# SD.net
KiCad netlist of a schematic drawn in Altium Designer
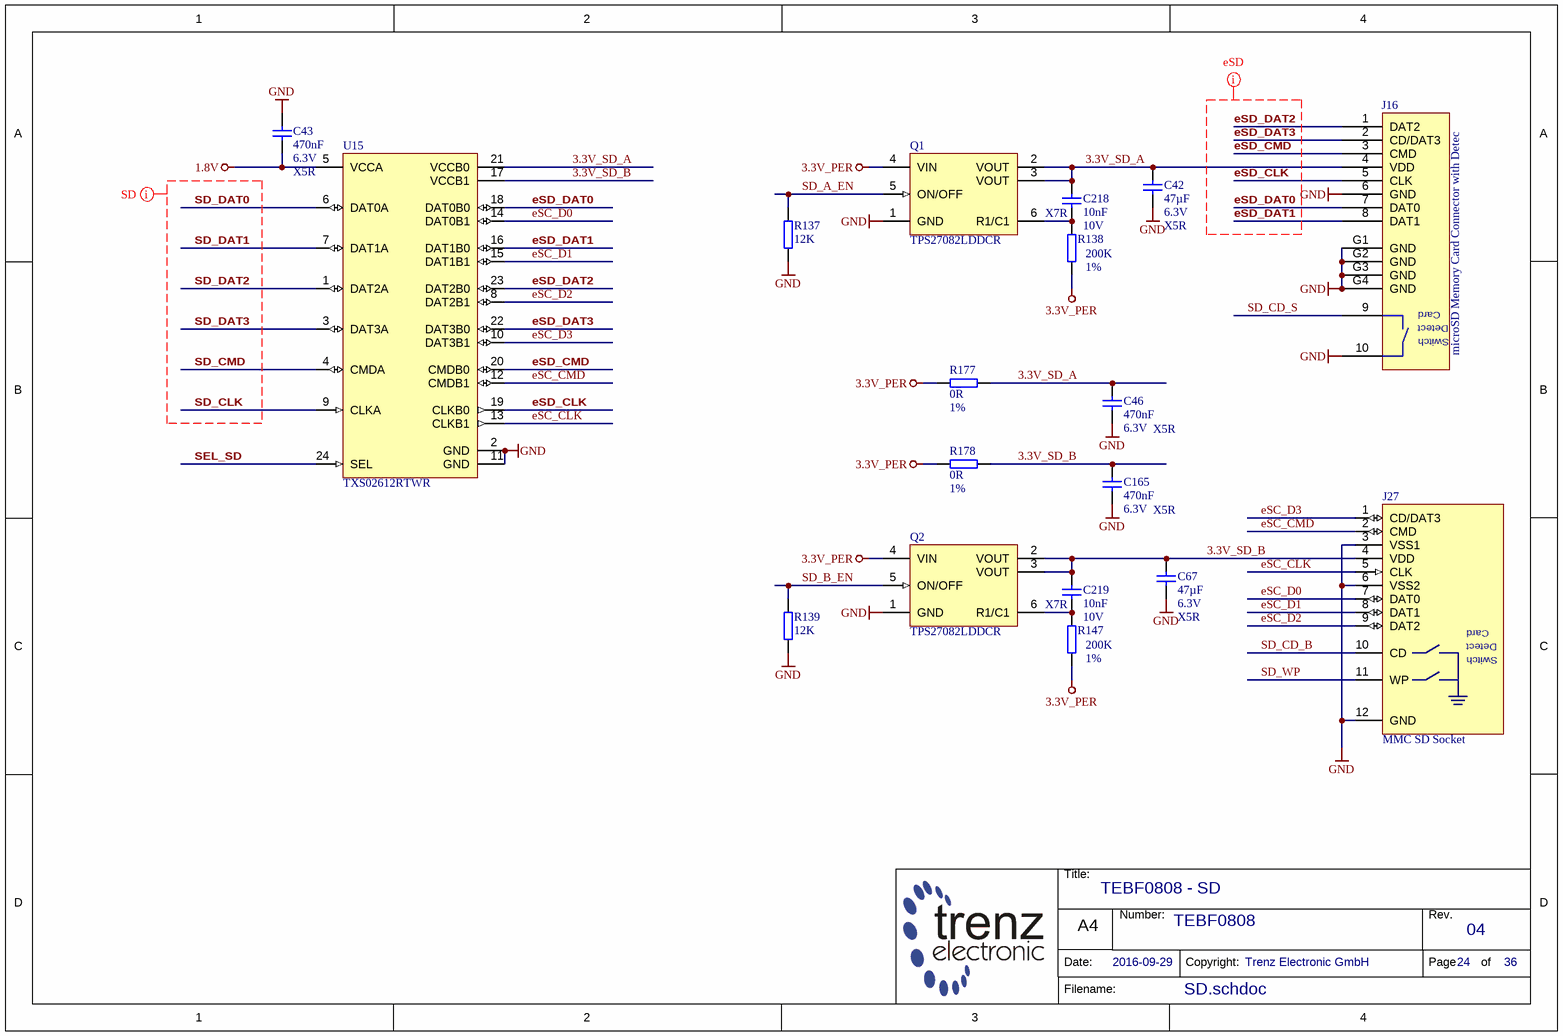
[diagram p0: SD.schdoc]

(export (version "E")
  (design (tool "Eeschema 10.0.6"))
  (components
    (comp (ref "C42")
      (value "47µF")
      (footprint "CAPC3216X180N")
      (description "KON 47µF 6.3V  X5R SMD 20%")
      (fields
        (field (name "VOLTAGE") "6.3V")
        (field (name "TECHNOLOGY") "X5R")
        (field (name "TOLERANCE") "20%")
      )
      (libsource (lib "TE") (part "CAP-NP"))
    )
    (comp (ref "C43")
      (value "470nF")
      (footprint "CAPC1005X55N")
      (description "KON 470nF 6,3V X5R SMD")
      (fields (field (name "VOLTAGE") "6.3V") (field (name "TECHNOLOGY") "X5R"))
      (libsource (lib "TE") (part "CAP-NP"))
    )
    (comp (ref "C46")
      (value "470nF")
      (footprint "CAPC1005X55N")
      (description "KON 470nF 6,3V X5R SMD")
      (fields (field (name "VOLTAGE") "6.3V") (field (name "TECHNOLOGY") "X5R"))
      (libsource (lib "TE") (part "CAP-NP"))
    )
    (comp (ref "C67")
      (value "47µF")
      (footprint "CAPC3216X180N")
      (description "KON 47µF 6.3V  X5R SMD 20%")
      (fields
        (field (name "VOLTAGE") "6.3V")
        (field (name "TECHNOLOGY") "X5R")
        (field (name "TOLERANCE") "20%")
      )
      (libsource (lib "TE") (part "CAP-NP"))
    )
    (comp (ref "C165")
      (value "470nF")
      (footprint "CAPC1005X55N")
      (description "KON 470nF 6,3V X5R SMD")
      (fields (field (name "VOLTAGE") "6.3V") (field (name "TECHNOLOGY") "X5R"))
      (libsource (lib "TE") (part "CAP-NP"))
    )
    (comp (ref "C218")
      (value "10nF")
      (footprint "CAPC0603X33N")
      (description "KON 10nF X7R 10V SMD 10%")
      (fields
        (field (name "VOLTAGE") "10V")
        (field (name "TECHNOLOGY") "X7R")
        (field (name "TOLERANCE") "10%")
      )
      (libsource (lib "TE") (part "CAP-NP"))
    )
    (comp (ref "C219")
      (value "10nF")
      (footprint "CAPC0603X33N")
      (description "KON 10nF X7R 10V SMD 10%")
      (fields
        (field (name "VOLTAGE") "10V")
        (field (name "TECHNOLOGY") "X7R")
        (field (name "TOLERANCE") "10%")
      )
      (libsource (lib "TE") (part "CAP-NP"))
    )
    (comp (ref "J16")
      (value "microSD Memory Card Connector with Detec")
      (footprint "104031-0811")
      (description "microSD Memory Card Connector with Detect Switch")
      (libsource (lib "TE") (part "104031-0811"))
    )
    (comp (ref "J27")
      (value "MMC SD Socket")
      (footprint "104C-TAA0-R")
      (description "MCC SD Socket")
      (libsource (lib "TE") (part "104C-TAA0-R"))
    )
    (comp (ref "Q1")
      (value "TPS27082LDDCR")
      (footprint "SOT95P280X110-6N")
      (libsource (lib "TE") (part "TPS27082LDDCR"))
    )
    (comp (ref "Q2")
      (value "TPS27082LDDCR")
      (footprint "SOT95P280X110-6N")
      (libsource (lib "TE") (part "TPS27082LDDCR"))
    )
    (comp (ref "R137")
      (value "12K")
      (footprint "RESC1005X40N")
      (description "WID SMD 12K 1% 0,063W")
      (fields (field (name "TOLERANCE") "1%"))
      (libsource (lib "TE") (part "RES"))
    )
    (comp (ref "R138")
      (value "200K")
      (footprint "RESC1005X40N")
      (description "WID SMD 200K 1% 0,063W")
      (fields (field (name "TOLERANCE") "1%"))
      (libsource (lib "TE") (part "RES"))
    )
    (comp (ref "R139")
      (value "12K")
      (footprint "RESC1005X40N")
      (description "WID SMD 12K 1% 0,063W")
      (fields (field (name "TOLERANCE") "1%"))
      (libsource (lib "TE") (part "RES"))
    )
    (comp (ref "R147")
      (value "200K")
      (footprint "RESC1005X40N")
      (description "WID SMD 200K 1% 0,063W")
      (fields (field (name "TOLERANCE") "1%"))
      (libsource (lib "TE") (part "RES"))
    )
    (comp (ref "R177")
      (value "0R")
      (footprint "RESC1005X40N")
      (description "WID SMD 0R")
      (fields (field (name "TOLERANCE") "1%"))
      (libsource (lib "TE") (part "RES"))
    )
    (comp (ref "R178")
      (value "0R")
      (footprint "RESC1005X40N")
      (description "WID SMD 0R")
      (fields (field (name "TOLERANCE") "1%"))
      (libsource (lib "TE") (part "RES"))
    )
    (comp (ref "U15")
      (value "TXS02612RTWR")
      (footprint "QFN50P400X400X80-25N-255")
      (libsource (lib "TE") (part "TXS02612RTWR"))
    )
  )
  (nets
    (net (code "1") (name "/3.3V_SD_A") (class "Default")
      (node (ref "C218") (pin "1") (pinfunction "1_1") (pintype "passive"))
      (node (ref "C42") (pin "1") (pinfunction "1_1") (pintype "passive"))
      (node (ref "C46") (pin "2") (pinfunction "2_2") (pintype "passive"))
      (node (ref "J16") (pin "4") (pinfunction "VDD_4") (pintype "passive"))
      (node (ref "Q1") (pin "2") (pinfunction "VOUT_2") (pintype "power_in"))
      (node (ref "Q1") (pin "3") (pinfunction "VOUT_3") (pintype "power_in"))
      (node (ref "R177") (pin "2") (pinfunction "2_2") (pintype "passive"))
      (node (ref "U15") (pin "21") (pinfunction "VCCB0_21") (pintype "power_in"))
    )
    (net (code "2") (name "/3.3V_SD_B") (class "Default")
      (node (ref "C165") (pin "2") (pinfunction "2_2") (pintype "passive"))
      (node (ref "C219") (pin "1") (pinfunction "1_1") (pintype "passive"))
      (node (ref "C67") (pin "1") (pinfunction "1_1") (pintype "passive"))
      (node (ref "J27") (pin "4") (pinfunction "VDD_4") (pintype "power_in"))
      (node (ref "Q2") (pin "2") (pinfunction "VOUT_2") (pintype "power_in"))
      (node (ref "Q2") (pin "3") (pinfunction "VOUT_3") (pintype "power_in"))
      (node (ref "R178") (pin "2") (pinfunction "2_2") (pintype "passive"))
      (node (ref "U15") (pin "17") (pinfunction "VCCB1_17") (pintype "power_in"))
    )
    (net (code "3") (name "/SD_A_EN") (class "Default")
      (node (ref "Q1") (pin "5") (pinfunction "ON/OFF_5") (pintype "input"))
      (node (ref "R137") (pin "1") (pinfunction "1_1") (pintype "passive"))
    )
    (net (code "4") (name "/SD_B_EN") (class "Default")
      (node (ref "Q2") (pin "5") (pinfunction "ON/OFF_5") (pintype "input"))
      (node (ref "R139") (pin "1") (pinfunction "1_1") (pintype "passive"))
    )
    (net (code "5") (name "/SD_CD_B") (class "Default")
      (node (ref "J27") (pin "10") (pinfunction "CD_10") (pintype "passive"))
    )
    (net (code "6") (name "/SD_CD_S") (class "Default")
      (node (ref "J16") (pin "9") (pinfunction "CDSW_9") (pintype "passive"))
    )
    (net (code "7") (name "/SD_CLK") (class "Default")
      (node (ref "U15") (pin "9") (pinfunction "CLKA_9") (pintype "input"))
    )
    (net (code "8") (name "/SD_CMD") (class "Default")
      (node (ref "U15") (pin "4") (pinfunction "CMDA_4") (pintype "bidirectional"))
    )
    (net (code "9") (name "/SD_DAT0") (class "Default")
      (node (ref "U15") (pin "6") (pinfunction "DAT0A_6") (pintype "bidirectional"))
    )
    (net (code "10") (name "/SD_DAT1") (class "Default")
      (node (ref "U15") (pin "7") (pinfunction "DAT1A_7") (pintype "bidirectional"))
    )
    (net (code "11") (name "/SD_DAT2") (class "Default")
      (node (ref "U15") (pin "1") (pinfunction "DAT2A_1") (pintype "bidirectional"))
    )
    (net (code "12") (name "/SD_DAT3") (class "Default")
      (node (ref "U15") (pin "3") (pinfunction "DAT3A_3") (pintype "bidirectional"))
    )
    (net (code "13") (name "/SD_WP") (class "Default")
      (node (ref "J27") (pin "11") (pinfunction "WP_11") (pintype "passive"))
    )
    (net (code "14") (name "/SEL_SD") (class "Default")
      (node (ref "U15") (pin "24") (pinfunction "SEL_24") (pintype "input"))
    )
    (net (code "15") (name "/eSC_CLK") (class "Default")
      (node (ref "J27") (pin "5") (pinfunction "CLK_5") (pintype "input"))
      (node (ref "U15") (pin "13") (pinfunction "CLKB1_13") (pintype "output"))
    )
    (net (code "16") (name "/eSC_CMD") (class "Default")
      (node (ref "J27") (pin "2") (pinfunction "CMD_2") (pintype "bidirectional"))
      (node (ref "U15") (pin "12") (pinfunction "CMDB1_12") (pintype "bidirectional"))
    )
    (net (code "17") (name "/eSC_D0") (class "Default")
      (node (ref "J27") (pin "7") (pinfunction "DAT0_7") (pintype "bidirectional"))
      (node (ref "U15") (pin "14") (pinfunction "DAT0B1_14") (pintype "bidirectional"))
    )
    (net (code "18") (name "/eSC_D1") (class "Default")
      (node (ref "J27") (pin "8") (pinfunction "DAT1_8") (pintype "bidirectional"))
      (node (ref "U15") (pin "15") (pinfunction "DAT1B1_15") (pintype "bidirectional"))
    )
    (net (code "19") (name "/eSC_D2") (class "Default")
      (node (ref "J27") (pin "9") (pinfunction "DAT2_9") (pintype "bidirectional"))
      (node (ref "U15") (pin "8") (pinfunction "DAT2B1_8") (pintype "bidirectional"))
    )
    (net (code "20") (name "/eSC_D3") (class "Default")
      (node (ref "J27") (pin "1") (pinfunction "CD/DAT3_1") (pintype "bidirectional"))
      (node (ref "U15") (pin "10") (pinfunction "DAT3B1_10") (pintype "bidirectional"))
    )
    (net (code "21") (name "/eSD_CLK") (class "Default")
      (node (ref "J16") (pin "5") (pinfunction "CLK_5") (pintype "passive"))
      (node (ref "U15") (pin "19") (pinfunction "CLKB0_19") (pintype "output"))
    )
    (net (code "22") (name "/eSD_CMD") (class "Default")
      (node (ref "J16") (pin "3") (pinfunction "CMD_3") (pintype "passive"))
      (node (ref "U15") (pin "20") (pinfunction "CMDB0_20") (pintype "bidirectional"))
    )
    (net (code "23") (name "/eSD_DAT0") (class "Default")
      (node (ref "J16") (pin "7") (pinfunction "DAT0_7") (pintype "passive"))
      (node (ref "U15") (pin "18") (pinfunction "DAT0B0_18") (pintype "bidirectional"))
    )
    (net (code "24") (name "/eSD_DAT1") (class "Default")
      (node (ref "J16") (pin "8") (pinfunction "DAT1_8") (pintype "passive"))
      (node (ref "U15") (pin "16") (pinfunction "DAT1B0_16") (pintype "bidirectional"))
    )
    (net (code "25") (name "/eSD_DAT2") (class "Default")
      (node (ref "J16") (pin "1") (pinfunction "DAT2_1") (pintype "passive"))
      (node (ref "U15") (pin "23") (pinfunction "DAT2B0_23") (pintype "bidirectional"))
    )
    (net (code "26") (name "/eSD_DAT3") (class "Default")
      (node (ref "J16") (pin "2") (pinfunction "CD/DAT3_2") (pintype "passive"))
      (node (ref "U15") (pin "22") (pinfunction "DAT3B0_22") (pintype "bidirectional"))
    )
    (net (code "27") (name "1.8V") (class "Default")
      (node (ref "C43") (pin "1") (pinfunction "1_1") (pintype "passive"))
      (node (ref "U15") (pin "5") (pinfunction "VCCA_5") (pintype "power_in"))
    )
    (net (code "28") (name "3.3V_PER") (class "Default")
      (node (ref "Q1") (pin "4") (pinfunction "VIN_4") (pintype "power_in"))
      (node (ref "Q2") (pin "4") (pinfunction "VIN_4") (pintype "power_in"))
      (node (ref "R138") (pin "2") (pinfunction "2_2") (pintype "passive"))
      (node (ref "R147") (pin "2") (pinfunction "2_2") (pintype "passive"))
      (node (ref "R177") (pin "1") (pinfunction "1_1") (pintype "passive"))
      (node (ref "R178") (pin "1") (pinfunction "1_1") (pintype "passive"))
    )
    (net (code "29") (name "GND") (class "Default")
      (node (ref "C165") (pin "1") (pinfunction "1_1") (pintype "passive"))
      (node (ref "C42") (pin "2") (pinfunction "2_2") (pintype "passive"))
      (node (ref "C43") (pin "2") (pinfunction "2_2") (pintype "passive"))
      (node (ref "C46") (pin "1") (pinfunction "1_1") (pintype "passive"))
      (node (ref "C67") (pin "2") (pinfunction "2_2") (pintype "passive"))
      (node (ref "J16") (pin "10") (pinfunction "CDSW_10") (pintype "passive"))
      (node (ref "J16") (pin "6") (pinfunction "GND_6") (pintype "passive"))
      (node (ref "J16") (pin "G1") (pinfunction "GND_G1") (pintype "passive"))
      (node (ref "J16") (pin "G2") (pinfunction "GND_G2") (pintype "passive"))
      (node (ref "J16") (pin "G3") (pinfunction "GND_G3") (pintype "passive"))
      (node (ref "J16") (pin "G4") (pinfunction "GND_G4") (pintype "passive"))
      (node (ref "J27") (pin "12") (pinfunction "GND_12") (pintype "power_in"))
      (node (ref "J27") (pin "3") (pinfunction "VSS1_3") (pintype "power_in"))
      (node (ref "J27") (pin "6") (pinfunction "VSS2_6") (pintype "power_in"))
      (node (ref "Q1") (pin "1") (pinfunction "GND_1") (pintype "power_in"))
      (node (ref "Q2") (pin "1") (pinfunction "GND_1") (pintype "power_in"))
      (node (ref "R137") (pin "2") (pinfunction "2_2") (pintype "passive"))
      (node (ref "R139") (pin "2") (pinfunction "2_2") (pintype "passive"))
      (node (ref "U15") (pin "11") (pinfunction "GND_11") (pintype "power_in"))
      (node (ref "U15") (pin "2") (pinfunction "GND_2") (pintype "power_in"))
    )
    (net (code "30") (name "Net-(Q1-R1{slash}C1)") (class "Default")
      (node (ref "C218") (pin "2") (pinfunction "2_2") (pintype "passive"))
      (node (ref "Q1") (pin "6") (pinfunction "R1/C1_6") (pintype "power_in"))
      (node (ref "R138") (pin "1") (pinfunction "1_1") (pintype "passive"))
    )
    (net (code "31") (name "Net-(Q2-R1{slash}C1)") (class "Default")
      (node (ref "C219") (pin "2") (pinfunction "2_2") (pintype "passive"))
      (node (ref "Q2") (pin "6") (pinfunction "R1/C1_6") (pintype "power_in"))
      (node (ref "R147") (pin "1") (pinfunction "1_1") (pintype "passive"))
    )
  )
)
